# MCU.net
KiCad netlist of a schematic drawn in Altium Designer
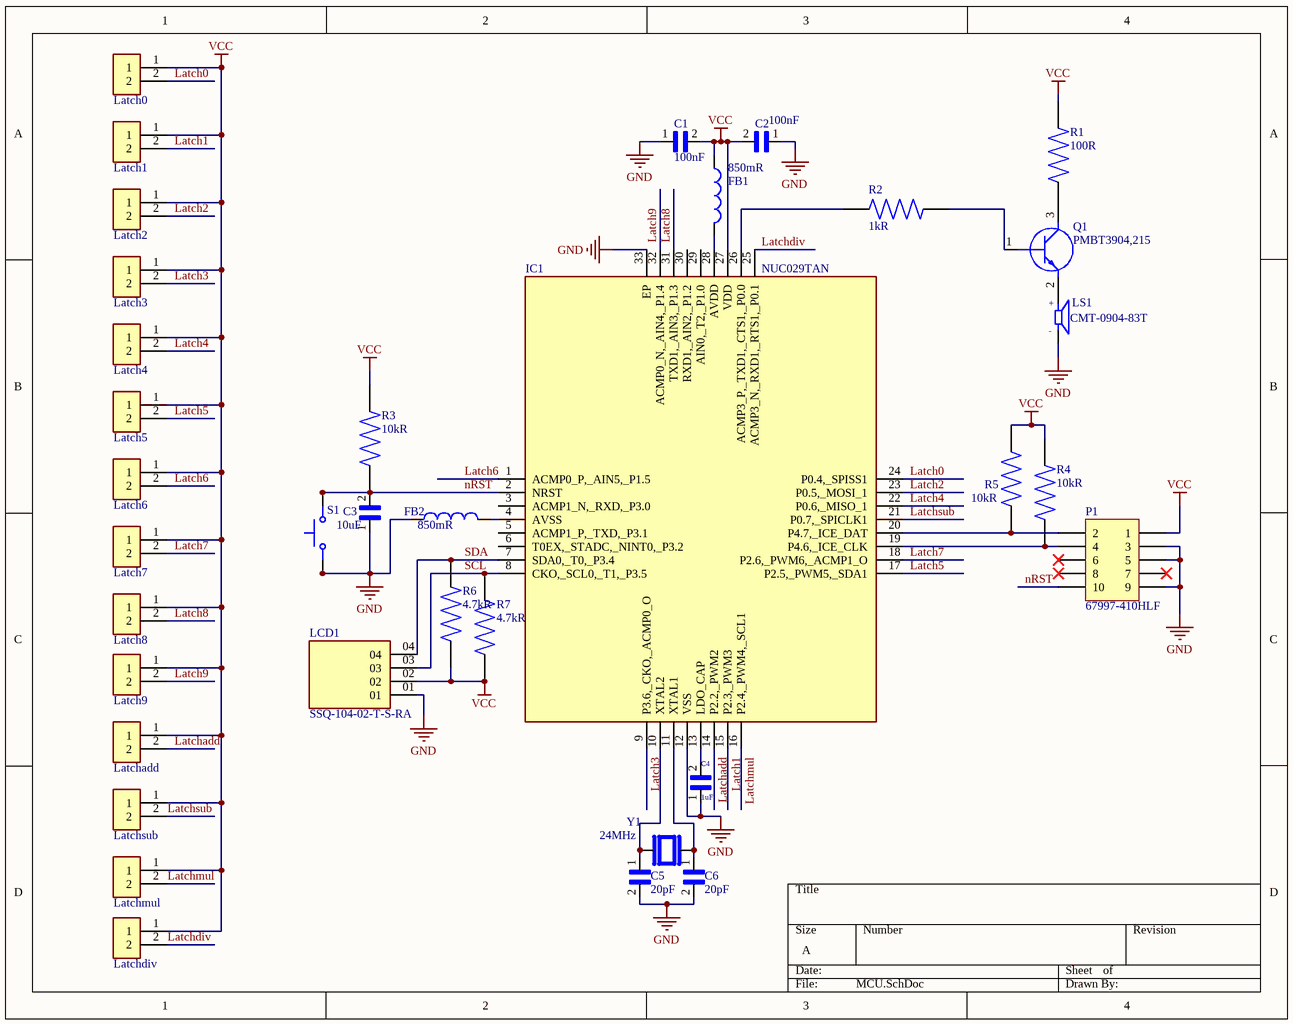
[diagram p0: MCU.SchDoc]

(export (version "E")
  (design (tool "Eeschema 10.0.6"))
  (components
    (comp (ref "C1")
      (value "100nF")
      (footprint "CAPC1005X55N")
      (description "Prices include import duty and tax. CAP, 0.1UF, 25V, MLCC, 0402; SVHC: No SVHC (15-Jan-2019)")
      (fields
        (field (name "MANUFACTURER") "Samsung")
        (field (name "MANUFACTURER PART NUMBER") "CL05A104KA5NNNC")
      )
      (libsource (lib "SnapEDA_Library") (part "CL05A104KA5NNNC"))
    )
    (comp (ref "C2")
      (value "100nF")
      (footprint "CAPC1005X55N")
      (description "Prices include import duty and tax. CAP, 0.1UF, 25V, MLCC, 0402; SVHC: No SVHC (15-Jan-2019)")
      (fields
        (field (name "MANUFACTURER") "Samsung")
        (field (name "MANUFACTURER PART NUMBER") "CL05A104KA5NNNC")
      )
      (libsource (lib "") (part "CL05A104KA5NNNC_1"))
    )
    (comp (ref "C3")
      (value "10uF")
      (footprint "CAPC2012X140N")
      (fields
        (field (name "MANUFACTURER") "Murata")
        (field (name "MANUFACTURER PART NUMBER") "GRM21BR61E106MA73L")
        (field (name "TOLERANCE") "20%")
      )
      (libsource (lib "SnapEDA_Library") (part "GRM21BR61E106MA73L"))
    )
    (comp (ref "C4")
      (value "1uF")
      (footprint "CAPC1005X55N")
      (description "Cap Ceramic 1uF 10V X5R 10% Pad SMD 0402 85°C T/R")
      (fields
        (field (name "MANUFACTURER") "Taiyo Yuden")
        (field (name "MANUFACTURER PART NUMBER") "LMK105BJ105KV-F")
      )
      (libsource (lib "SnapEDA_Library") (part "LMK105BJ105KV-F"))
    )
    (comp (ref "C5")
      (value "20pF")
      (footprint "CAPC1005X55N")
      (description "CAP CER 20PF 50V C0G/NP0 0402")
      (fields
        (field (name "MANUFACTURER") "Murata")
        (field (name "MANUFACTURER PART NUMBER") "GRM1555C1H200JA01D")
      )
      (libsource (lib "SnapEDA_Library") (part "GRM1555C1H200JA01D"))
    )
    (comp (ref "C6")
      (value "20pF")
      (footprint "CAPC1005X55N")
      (description "CAP CER 20PF 50V C0G/NP0 0402")
      (fields
        (field (name "MANUFACTURER") "Murata")
        (field (name "MANUFACTURER PART NUMBER") "GRM1555C1H200JA01D")
      )
      (libsource (lib "SnapEDA_Library") (part "GRM1555C1H200JA01D"))
    )
    (comp (ref "FB1")
      (value "850mR")
      (footprint "0603")
      (description "FERRITE BEAD 1 KOHM 0603 1 LN")
      (fields
        (field (name "MANUFACTURER") "Murata")
        (field (name "MANUFACTURER PART NUMBER") "BLM18BD102BH1D")
      )
      (libsource (lib "Miscellaneous Devices") (part "Inductor"))
    )
    (comp (ref "FB2")
      (value "850mR")
      (footprint "0603")
      (description "FERRITE BEAD 1 KOHM 0603 1 LN")
      (fields
        (field (name "MANUFACTURER") "Murata")
        (field (name "MANUFACTURER PART NUMBER") "BLM18BD102BH1D")
      )
      (libsource (lib "") (part "Inductor_1"))
    )
    (comp (ref "IC1")
      (value "NUC029TAN")
      (footprint "SamacSys:QFN40P400X400X80-33N")
      (description "Integrated Circuit")
      (fields (field (name "MANUFACTURER") "Nuvoton"))
      (libsource (lib "*") (part "NUC029TAN"))
    )
    (comp (ref "Latch0")
      (value "~")
      (footprint "JST_B2B-PH-K-S(LF)(SN)")
      (description "Connector Header, PH Series, 2 Position, 2.00mm, Through Hole, Press-Fit, Solder, Natural")
      (fields (field (name "MANUFACTURER") "JST") (field (name "MANUFACTURER PART NUMBER") "B2BPHKSLFSN"))
      (libsource (lib "Mathcube_PCB") (part "B2B-PH-K-S(LF)(SN)"))
    )
    (comp (ref "Latch1")
      (value "B2B-PH-K-S(LF)(SN)")
      (footprint "JST_B2B-PH-K-S(LF)(SN)")
      (description "Connector Header, PH Series, 2 Position, 2.00mm, Through Hole, Press-Fit, Solder, Natural")
      (fields (field (name "MANUFACTURER") "JST") (field (name "MANUFACTURER PART NUMBER") "B2BPHKSLFSN"))
      (libsource (lib "Mathcube_PCB") (part "B2B-PH-K-S(LF)(SN)"))
    )
    (comp (ref "Latch2")
      (value "B2B-PH-K-S(LF)(SN)")
      (footprint "JST_B2B-PH-K-S(LF)(SN)")
      (description "Connector Header, PH Series, 2 Position, 2.00mm, Through Hole, Press-Fit, Solder, Natural")
      (fields (field (name "MANUFACTURER") "JST") (field (name "MANUFACTURER PART NUMBER") "B2BPHKSLFSN"))
      (libsource (lib "Mathcube_PCB") (part "B2B-PH-K-S(LF)(SN)"))
    )
    (comp (ref "Latch3")
      (value "B2B-PH-K-S(LF)(SN)")
      (footprint "JST_B2B-PH-K-S(LF)(SN)")
      (description "Connector Header, PH Series, 2 Position, 2.00mm, Through Hole, Press-Fit, Solder, Natural")
      (fields (field (name "MANUFACTURER") "JST") (field (name "MANUFACTURER PART NUMBER") "B2BPHKSLFSN"))
      (libsource (lib "Mathcube_PCB") (part "B2B-PH-K-S(LF)(SN)"))
    )
    (comp (ref "Latch4")
      (value "B2B-PH-K-S(LF)(SN)")
      (footprint "JST_B2B-PH-K-S(LF)(SN)")
      (description "Connector Header, PH Series, 2 Position, 2.00mm, Through Hole, Press-Fit, Solder, Natural")
      (fields (field (name "MANUFACTURER") "JST") (field (name "MANUFACTURER PART NUMBER") "B2BPHKSLFSN"))
      (libsource (lib "Mathcube_PCB") (part "B2B-PH-K-S(LF)(SN)"))
    )
    (comp (ref "Latch5")
      (value "B2B-PH-K-S(LF)(SN)")
      (footprint "JST_B2B-PH-K-S(LF)(SN)")
      (description "Connector Header, PH Series, 2 Position, 2.00mm, Through Hole, Press-Fit, Solder, Natural")
      (fields (field (name "MANUFACTURER") "JST") (field (name "MANUFACTURER PART NUMBER") "B2BPHKSLFSN"))
      (libsource (lib "Mathcube_PCB") (part "B2B-PH-K-S(LF)(SN)"))
    )
    (comp (ref "Latch6")
      (value "B2B-PH-K-S(LF)(SN)")
      (footprint "JST_B2B-PH-K-S(LF)(SN)")
      (description "Connector Header, PH Series, 2 Position, 2.00mm, Through Hole, Press-Fit, Solder, Natural")
      (fields (field (name "MANUFACTURER") "JST") (field (name "MANUFACTURER PART NUMBER") "B2BPHKSLFSN"))
      (libsource (lib "Mathcube_PCB") (part "B2B-PH-K-S(LF)(SN)"))
    )
    (comp (ref "Latch7")
      (value "B2B-PH-K-S(LF)(SN)")
      (footprint "JST_B2B-PH-K-S(LF)(SN)")
      (description "Connector Header, PH Series, 2 Position, 2.00mm, Through Hole, Press-Fit, Solder, Natural")
      (fields (field (name "MANUFACTURER") "JST") (field (name "MANUFACTURER PART NUMBER") "B2BPHKSLFSN"))
      (libsource (lib "Mathcube_PCB") (part "B2B-PH-K-S(LF)(SN)"))
    )
    (comp (ref "Latch8")
      (value "B2B-PH-K-S(LF)(SN)")
      (footprint "JST_B2B-PH-K-S(LF)(SN)")
      (description "Connector Header, PH Series, 2 Position, 2.00mm, Through Hole, Press-Fit, Solder, Natural")
      (fields (field (name "MANUFACTURER") "JST") (field (name "MANUFACTURER PART NUMBER") "B2BPHKSLFSN"))
      (libsource (lib "Mathcube_PCB") (part "B2B-PH-K-S(LF)(SN)"))
    )
    (comp (ref "Latch9")
      (value "B2B-PH-K-S(LF)(SN)")
      (footprint "JST_B2B-PH-K-S(LF)(SN)")
      (description "Connector Header, PH Series, 2 Position, 2.00mm, Through Hole, Press-Fit, Solder, Natural")
      (fields (field (name "MANUFACTURER") "JST") (field (name "MANUFACTURER PART NUMBER") "B2BPHKSLFSN"))
      (libsource (lib "Mathcube_PCB") (part "B2B-PH-K-S(LF)(SN)"))
    )
    (comp (ref "Latchadd")
      (value "B2B-PH-K-S(LF)(SN)")
      (footprint "JST_B2B-PH-K-S(LF)(SN)")
      (description "Connector Header, PH Series, 2 Position, 2.00mm, Through Hole, Press-Fit, Solder, Natural")
      (fields (field (name "MANUFACTURER") "JST") (field (name "MANUFACTURER PART NUMBER") "B2BPHKSLFSN"))
      (libsource (lib "Mathcube_PCB") (part "B2B-PH-K-S(LF)(SN)"))
    )
    (comp (ref "Latchdiv")
      (value "B2B-PH-K-S(LF)(SN)")
      (footprint "JST_B2B-PH-K-S(LF)(SN)")
      (description "Connector Header, PH Series, 2 Position, 2.00mm, Through Hole, Press-Fit, Solder, Natural")
      (fields (field (name "MANUFACTURER") "JST") (field (name "MANUFACTURER PART NUMBER") "B2BPHKSLFSN"))
      (libsource (lib "Mathcube_PCB") (part "B2B-PH-K-S(LF)(SN)"))
    )
    (comp (ref "Latchmul")
      (value "B2B-PH-K-S(LF)(SN)")
      (footprint "JST_B2B-PH-K-S(LF)(SN)")
      (description "Connector Header, PH Series, 2 Position, 2.00mm, Through Hole, Press-Fit, Solder, Natural")
      (fields (field (name "MANUFACTURER") "JST") (field (name "MANUFACTURER PART NUMBER") "B2BPHKSLFSN"))
      (libsource (lib "Mathcube_PCB") (part "B2B-PH-K-S(LF)(SN)"))
    )
    (comp (ref "Latchsub")
      (value "B2B-PH-K-S(LF)(SN)")
      (footprint "JST_B2B-PH-K-S(LF)(SN)")
      (description "Connector Header, PH Series, 2 Position, 2.00mm, Through Hole, Press-Fit, Solder, Natural")
      (fields (field (name "MANUFACTURER") "JST") (field (name "MANUFACTURER PART NUMBER") "B2BPHKSLFSN"))
      (libsource (lib "Mathcube_PCB") (part "B2B-PH-K-S(LF)(SN)"))
    )
    (comp (ref "LCD1")
      (value "SSQ-104-02-T-S-RA")
      (footprint "SSQ-104-02-T-S-RA:SAMTEC_SSQ-104-02-T-S-RA")
      (description "Conn Socket Strip SKT 4 POS 2.54mm Solder RA Thru-Hole Bulk")
      (fields (field (name "MANUFACTURER") "Samtec"))
      (libsource (lib "*") (part "SSQ-104-02-T-S-RA"))
    )
    (comp (ref "LS1")
      (value "CMT-0904-83T")
      (footprint "XDCR_CMT-0904-83T")
      (fields (field (name "MANUFACTURER") "CUI Devices"))
      (libsource (lib "SnapEDA_Library") (part "CMT-0904-83T"))
    )
    (comp (ref "P1")
      (value "67997-410HLF")
      (footprint "HDR2X5")
      (description "Conn Unshrouded Header HDR 10 POS 2.54mm Solder ST Top Entry Thru-Hole BergStik® Bulk")
      (fields (field (name "MANUFACTURER") "ICC"))
      (libsource (lib "Miscellaneous Connectors") (part "Header 5X2"))
    )
    (comp (ref "Q1")
      (value "PMBT3904,215")
      (footprint "SamacSys:SOT95P230X110-3N")
      (description "Transistor BJT NPN")
      (fields
        (field (name "MOUSER PART NUMBER") "771-PMBT3904-T/R")
        (field (name "MANUFACTURER") "CUI Devices")
      )
      (libsource (lib "*") (part "PMBT3904,215"))
    )
    (comp (ref "R1")
      (value "100R")
      (footprint "RESC1005X35N")
      (description "RES 100 OHM 1% 1/16W 0402")
      (fields
        (field (name "MANUFACTURER") "Stackpole Electronics")
        (field (name "MANUFACTURER PART NUMBER") "RMCF0402FT100R")
      )
      (libsource (lib "SnapEDA_Library") (part "RMCF0402FT100R"))
    )
    (comp (ref "R2")
      (value "1kR")
      (footprint "RESC1005X35N")
      (description "RES 1K OHM 1% 1/16W 0402")
      (fields
        (field (name "MANUFACTURER") "Stackpole Electronics")
        (field (name "MANUFACTURER PART NUMBER") "RMCF0402FT1K00")
      )
      (libsource (lib "SnapEDA_Library") (part "RMCF0402FT100R"))
    )
    (comp (ref "R3")
      (value "10kR")
      (footprint "RESC1005X40")
      (description "RES 10K OHM 5% 1/16W 0402")
      (fields
        (field (name "MANUFACTURER") "Stackpole Electronics")
        (field (name "MANUFACTURER PART NUMBER") "RMCF0402JT10K0")
      )
      (libsource (lib "SnapEDA_Library") (part "RMCF0402JT10K0"))
    )
    (comp (ref "R4")
      (value "10kR")
      (footprint "RESC1005X40")
      (description "RES 10K OHM 5% 1/16W 0402")
      (fields
        (field (name "MANUFACTURER") "Stackpole Electronics")
        (field (name "MANUFACTURER PART NUMBER") "RMCF0402JT10K0")
      )
      (libsource (lib "SnapEDA_Library") (part "RMCF0402JT10K0"))
    )
    (comp (ref "R5")
      (value "10kR")
      (footprint "RESC1005X40")
      (description "RES 10K OHM 5% 1/16W 0402")
      (fields
        (field (name "MANUFACTURER") "Stackpole Electronics")
        (field (name "MANUFACTURER PART NUMBER") "RMCF0402JT10K0")
      )
      (libsource (lib "SnapEDA_Library") (part "RMCF0402JT10K0"))
    )
    (comp (ref "R6")
      (value "4.7kR")
      (footprint "RMCF0402JT4K70:RESC1005X40")
      (description "Res Thick Film 0402 4.7K Ohm 5% 1/16W 100ppm/C Molded SMD SMD Paper T/R")
      (fields
        (field (name "MANUFACTURER") "Stackpole Electronics")
        (field (name "MANUFACTURER PART NUMBER") "RMCF0402JT4K70")
      )
      (libsource (lib "*") (part "RMCF0402JT4K70"))
    )
    (comp (ref "R7")
      (value "4.7kR")
      (footprint "RMCF0402JT4K70:RESC1005X40")
      (description "Res Thick Film 0402 4.7K Ohm 5% 1/16W 100ppm/C Molded SMD SMD Paper T/R")
      (fields
        (field (name "MANUFACTURER") "Stackpole Electronics")
        (field (name "MANUFACTURER PART NUMBER") "RMCF0402JT4K70")
      )
      (libsource (lib "*") (part "RMCF0402JT4K70"))
    )
    (comp (ref "S1")
      (value "TL3315NF100Q")
      (footprint "TL3315NF100Q:SW_TL3315NF100Q")
      (description "E-SWITCH - TL3315NF100Q - SWITCH, TACTILE, SPST, 50mA, 15VDC")
      (fields (field (name "MANUFACTURER") "E-Switch"))
      (libsource (lib "*") (part "TL3315NF100Q"))
    )
    (comp (ref "Y1")
      (value "24MHz")
      (footprint "OSC_XRCGB24M000F0L00R0")
      (description "MURATA - XRCGB24M000F0L00R0 - QUARZRESONATOR, 24MHZ, 150PPM")
      (fields
        (field (name "MANUFACTURER") "Murata")
        (field (name "MANUFACTURER PART NUMBER") "XRCGB24M000F0L00R0")
      )
      (libsource (lib "SnapEDA_Library") (part "XRCGB24M000F0L00R0"))
    )
  )
  (nets
    (net (code "1") (name "/Latch0") (class "Default")
      (node (ref "IC1") (pin "24") (pinfunction "P0.4,_SPISS1_24") (pintype "passive"))
      (node (ref "Latch0") (pin "2") (pinfunction "2_2") (pintype "passive"))
    )
    (net (code "2") (name "/Latch1") (class "Default")
      (node (ref "IC1") (pin "15") (pinfunction "P2.3,_PWM3_15") (pintype "passive"))
      (node (ref "Latch1") (pin "2") (pinfunction "2_2") (pintype "passive"))
    )
    (net (code "3") (name "/Latch2") (class "Default")
      (node (ref "IC1") (pin "23") (pinfunction "P0.5,_MOSI_1_23") (pintype "passive"))
      (node (ref "Latch2") (pin "2") (pinfunction "2_2") (pintype "passive"))
    )
    (net (code "4") (name "/Latch3") (class "Default")
      (node (ref "IC1") (pin "9") (pinfunction "P3.6,_CKO,_ACMP0_O_9") (pintype "passive"))
      (node (ref "Latch3") (pin "2") (pinfunction "2_2") (pintype "passive"))
    )
    (net (code "5") (name "/Latch4") (class "Default")
      (node (ref "IC1") (pin "22") (pinfunction "P0.6,_MISO_1_22") (pintype "passive"))
      (node (ref "Latch4") (pin "2") (pinfunction "2_2") (pintype "passive"))
    )
    (net (code "6") (name "/Latch5") (class "Default")
      (node (ref "IC1") (pin "17") (pinfunction "P2.5,_PWM5,_SDA1_17") (pintype "passive"))
      (node (ref "Latch5") (pin "2") (pinfunction "2_2") (pintype "passive"))
    )
    (net (code "7") (name "/Latch6") (class "Default")
      (node (ref "IC1") (pin "1") (pinfunction "ACMP0_P,_AIN5,_P1.5_1") (pintype "passive"))
      (node (ref "Latch6") (pin "2") (pinfunction "2_2") (pintype "passive"))
    )
    (net (code "8") (name "/Latch7") (class "Default")
      (node (ref "IC1") (pin "18") (pinfunction "P2.6,_PWM6,_ACMP1_O_18") (pintype "passive"))
      (node (ref "Latch7") (pin "2") (pinfunction "2_2") (pintype "passive"))
    )
    (net (code "9") (name "/Latch8") (class "Default")
      (node (ref "IC1") (pin "31") (pinfunction "TXD1,_AIN3,_P1.3_31") (pintype "passive"))
      (node (ref "Latch8") (pin "2") (pinfunction "2_2") (pintype "passive"))
    )
    (net (code "10") (name "/Latch9") (class "Default")
      (node (ref "IC1") (pin "32") (pinfunction "ACMP0_N,_AIN4,_P1.4_32") (pintype "passive"))
      (node (ref "Latch9") (pin "2") (pinfunction "2_2") (pintype "passive"))
    )
    (net (code "11") (name "/Latchadd") (class "Default")
      (node (ref "IC1") (pin "14") (pinfunction "P2.2,_PWM2_14") (pintype "passive"))
      (node (ref "Latchadd") (pin "2") (pinfunction "2_2") (pintype "passive"))
    )
    (net (code "12") (name "/Latchdiv") (class "Default")
      (node (ref "IC1") (pin "25") (pinfunction "ACMP3_N,_RXD1,_RTS1,_P0.1_25") (pintype "passive"))
      (node (ref "Latchdiv") (pin "2") (pinfunction "2_2") (pintype "passive"))
    )
    (net (code "13") (name "/Latchmul") (class "Default")
      (node (ref "IC1") (pin "16") (pinfunction "P2.4,_PWM4,_SCL1_16") (pintype "passive"))
      (node (ref "Latchmul") (pin "2") (pinfunction "2_2") (pintype "passive"))
    )
    (net (code "14") (name "/Latchsub") (class "Default")
      (node (ref "IC1") (pin "21") (pinfunction "P0.7,_SPICLK1_21") (pintype "passive"))
      (node (ref "Latchsub") (pin "2") (pinfunction "2_2") (pintype "passive"))
    )
    (net (code "15") (name "/SCL") (class "Default")
      (node (ref "IC1") (pin "8") (pinfunction "CKO,_SCL0,_T1,_P3.5_8") (pintype "passive"))
      (node (ref "LCD1") (pin "03") (pinfunction "03_03") (pintype "passive"))
      (node (ref "R7") (pin "1") (pinfunction "1_1") (pintype "passive"))
    )
    (net (code "16") (name "/SDA") (class "Default")
      (node (ref "IC1") (pin "7") (pinfunction "SDA0,_T0,_P3.4_7") (pintype "passive"))
      (node (ref "LCD1") (pin "04") (pinfunction "04_04") (pintype "passive"))
      (node (ref "R6") (pin "1") (pinfunction "1_1") (pintype "passive"))
    )
    (net (code "17") (name "/nRST") (class "Default")
      (node (ref "C3") (pin "2") (pinfunction "2_2") (pintype "passive"))
      (node (ref "IC1") (pin "2") (pinfunction "NRST_2") (pintype "passive"))
      (node (ref "P1") (pin "10") (pinfunction "10_10") (pintype "passive"))
      (node (ref "R3") (pin "1") (pinfunction "1_1") (pintype "passive"))
      (node (ref "S1") (pin "3") (pinfunction "3_3") (pintype "passive"))
      (node (ref "S1") (pin "4") (pinfunction "3_4") (pintype "passive"))
    )
    (net (code "18") (name "GND") (class "Default")
      (node (ref "C1") (pin "1") (pinfunction "1_1") (pintype "passive"))
      (node (ref "C2") (pin "1") (pinfunction "1_1") (pintype "passive"))
      (node (ref "C3") (pin "1") (pinfunction "1_1") (pintype "passive"))
      (node (ref "C4") (pin "1") (pinfunction "1_1") (pintype "passive"))
      (node (ref "C5") (pin "2") (pinfunction "2_2") (pintype "passive"))
      (node (ref "C6") (pin "2") (pinfunction "2_2") (pintype "passive"))
      (node (ref "FB2") (pin "1") (pinfunction "1_1") (pintype "passive"))
      (node (ref "IC1") (pin "12") (pinfunction "VSS_12") (pintype "passive"))
      (node (ref "IC1") (pin "33") (pinfunction "EP_33") (pintype "passive"))
      (node (ref "LCD1") (pin "01") (pinfunction "01_01") (pintype "passive"))
      (node (ref "LS1") (pin "N") (pinfunction "N_N") (pintype "passive"))
      (node (ref "P1") (pin "3") (pinfunction "3_3") (pintype "passive"))
      (node (ref "P1") (pin "5") (pinfunction "5_5") (pintype "passive"))
      (node (ref "P1") (pin "9") (pinfunction "9_9") (pintype "passive"))
      (node (ref "S1") (pin "1") (pinfunction "1_1") (pintype "passive"))
      (node (ref "S1") (pin "2") (pinfunction "1_2") (pintype "passive"))
    )
    (net (code "19") (name "Net-(IC1-ACMP3_P,_TXD1,_CTS1,_P0.0)") (class "Default")
      (node (ref "IC1") (pin "26") (pinfunction "ACMP3_P,_TXD1,_CTS1,_P0.0_26") (pintype "passive"))
      (node (ref "R2") (pin "1") (pinfunction "1_1") (pintype "passive"))
    )
    (net (code "20") (name "Net-(IC1-AVDD)") (class "Default")
      (node (ref "FB1") (pin "1") (pinfunction "1_1") (pintype "passive"))
      (node (ref "IC1") (pin "28") (pinfunction "AVDD_28") (pintype "passive"))
    )
    (net (code "21") (name "Net-(IC1-AVSS)") (class "Default")
      (node (ref "FB2") (pin "2") (pinfunction "2_2") (pintype "passive"))
      (node (ref "IC1") (pin "4") (pinfunction "AVSS_4") (pintype "passive"))
    )
    (net (code "22") (name "Net-(IC1-LDO_CAP)") (class "Default")
      (node (ref "C4") (pin "2") (pinfunction "2_2") (pintype "passive"))
      (node (ref "IC1") (pin "13") (pinfunction "LDO_CAP_13") (pintype "passive"))
    )
    (net (code "23") (name "Net-(IC1-P4.6,_ICE_CLK)") (class "Default")
      (node (ref "IC1") (pin "19") (pinfunction "P4.6,_ICE_CLK_19") (pintype "passive"))
      (node (ref "P1") (pin "4") (pinfunction "4_4") (pintype "passive"))
      (node (ref "R4") (pin "1") (pinfunction "1_1") (pintype "passive"))
    )
    (net (code "24") (name "Net-(IC1-P4.7,_ICE_DAT)") (class "Default")
      (node (ref "IC1") (pin "20") (pinfunction "P4.7,_ICE_DAT_20") (pintype "passive"))
      (node (ref "P1") (pin "2") (pinfunction "2_2") (pintype "passive"))
      (node (ref "R5") (pin "1") (pinfunction "1_1") (pintype "passive"))
    )
    (net (code "25") (name "Net-(IC1-XTAL1)") (class "Default")
      (node (ref "C6") (pin "1") (pinfunction "1_1") (pintype "passive"))
      (node (ref "IC1") (pin "11") (pinfunction "XTAL1_11") (pintype "passive"))
      (node (ref "Y1") (pin "3") (pinfunction "3_3") (pintype "passive"))
    )
    (net (code "26") (name "Net-(IC1-XTAL2)") (class "Default")
      (node (ref "C5") (pin "1") (pinfunction "1_1") (pintype "passive"))
      (node (ref "IC1") (pin "10") (pinfunction "XTAL2_10") (pintype "passive"))
      (node (ref "Y1") (pin "1") (pinfunction "1_1") (pintype "passive"))
    )
    (net (code "27") (name "Net-(Q1-B)") (class "Default")
      (node (ref "Q1") (pin "1") (pinfunction "B_1") (pintype "passive"))
      (node (ref "R2") (pin "2") (pinfunction "2_2") (pintype "passive"))
    )
    (net (code "28") (name "Net-(Q1-C)") (class "Default")
      (node (ref "Q1") (pin "3") (pinfunction "C_3") (pintype "passive"))
      (node (ref "R1") (pin "1") (pinfunction "1_1") (pintype "passive"))
    )
    (net (code "29") (name "Net-(Q1-E)") (class "Default")
      (node (ref "LS1") (pin "P") (pinfunction "P_P") (pintype "passive"))
      (node (ref "Q1") (pin "2") (pinfunction "E_2") (pintype "passive"))
    )
    (net (code "30") (name "VCC") (class "Default")
      (node (ref "C1") (pin "2") (pinfunction "2_2") (pintype "passive"))
      (node (ref "C2") (pin "2") (pinfunction "2_2") (pintype "passive"))
      (node (ref "FB1") (pin "2") (pinfunction "2_2") (pintype "passive"))
      (node (ref "IC1") (pin "27") (pinfunction "VDD_27") (pintype "passive"))
      (node (ref "LCD1") (pin "02") (pinfunction "02_02") (pintype "passive"))
      (node (ref "Latch0") (pin "1") (pinfunction "1_1") (pintype "passive"))
      (node (ref "Latch1") (pin "1") (pinfunction "1_1") (pintype "passive"))
      (node (ref "Latch2") (pin "1") (pinfunction "1_1") (pintype "passive"))
      (node (ref "Latch3") (pin "1") (pinfunction "1_1") (pintype "passive"))
      (node (ref "Latch4") (pin "1") (pinfunction "1_1") (pintype "passive"))
      (node (ref "Latch5") (pin "1") (pinfunction "1_1") (pintype "passive"))
      (node (ref "Latch6") (pin "1") (pinfunction "1_1") (pintype "passive"))
      (node (ref "Latch7") (pin "1") (pinfunction "1_1") (pintype "passive"))
      (node (ref "Latch8") (pin "1") (pinfunction "1_1") (pintype "passive"))
      (node (ref "Latch9") (pin "1") (pinfunction "1_1") (pintype "passive"))
      (node (ref "Latchadd") (pin "1") (pinfunction "1_1") (pintype "passive"))
      (node (ref "Latchdiv") (pin "1") (pinfunction "1_1") (pintype "passive"))
      (node (ref "Latchmul") (pin "1") (pinfunction "1_1") (pintype "passive"))
      (node (ref "Latchsub") (pin "1") (pinfunction "1_1") (pintype "passive"))
      (node (ref "P1") (pin "1") (pinfunction "1_1") (pintype "passive"))
      (node (ref "R1") (pin "2") (pinfunction "2_2") (pintype "passive"))
      (node (ref "R3") (pin "2") (pinfunction "2_2") (pintype "passive"))
      (node (ref "R4") (pin "2") (pinfunction "2_2") (pintype "passive"))
      (node (ref "R5") (pin "2") (pinfunction "2_2") (pintype "passive"))
      (node (ref "R6") (pin "2") (pinfunction "2_2") (pintype "passive"))
      (node (ref "R7") (pin "2") (pinfunction "2_2") (pintype "passive"))
    )
    (net (code "31") (name "unconnected-(IC1-ACMP1_N,_RXD,_P3.0-Pad3)") (class "Default")
      (node (ref "IC1") (pin "3") (pinfunction "ACMP1_N,_RXD,_P3.0_3") (pintype "passive"))
    )
    (net (code "32") (name "unconnected-(IC1-ACMP1_P,_TXD,_P3.1-Pad5)") (class "Default")
      (node (ref "IC1") (pin "5") (pinfunction "ACMP1_P,_TXD,_P3.1_5") (pintype "passive"))
    )
    (net (code "33") (name "unconnected-(IC1-AIN0,_T2,_P1.0-Pad29)") (class "Default")
      (node (ref "IC1") (pin "29") (pinfunction "AIN0,_T2,_P1.0_29") (pintype "passive"))
    )
    (net (code "34") (name "unconnected-(IC1-RXD1,_AIN2,_P1.2-Pad30)") (class "Default")
      (node (ref "IC1") (pin "30") (pinfunction "RXD1,_AIN2,_P1.2_30") (pintype "passive"))
    )
    (net (code "35") (name "unconnected-(IC1-T0EX,_STADC,_NINT0,_P3.2-Pad6)") (class "Default")
      (node (ref "IC1") (pin "6") (pinfunction "T0EX,_STADC,_NINT0,_P3.2_6") (pintype "passive"))
    )
    (net (code "36") (name "unconnected-(P1-Pad6)") (class "Default")
      (node (ref "P1") (pin "6") (pinfunction "6_6") (pintype "passive+no_connect"))
    )
    (net (code "37") (name "unconnected-(P1-Pad7)") (class "Default")
      (node (ref "P1") (pin "7") (pinfunction "7_7") (pintype "passive+no_connect"))
    )
    (net (code "38") (name "unconnected-(P1-Pad8)") (class "Default")
      (node (ref "P1") (pin "8") (pinfunction "8_8") (pintype "passive+no_connect"))
    )
  )
)
